# Schematic.net
KiCad netlist of a schematic drawn in EAGLE
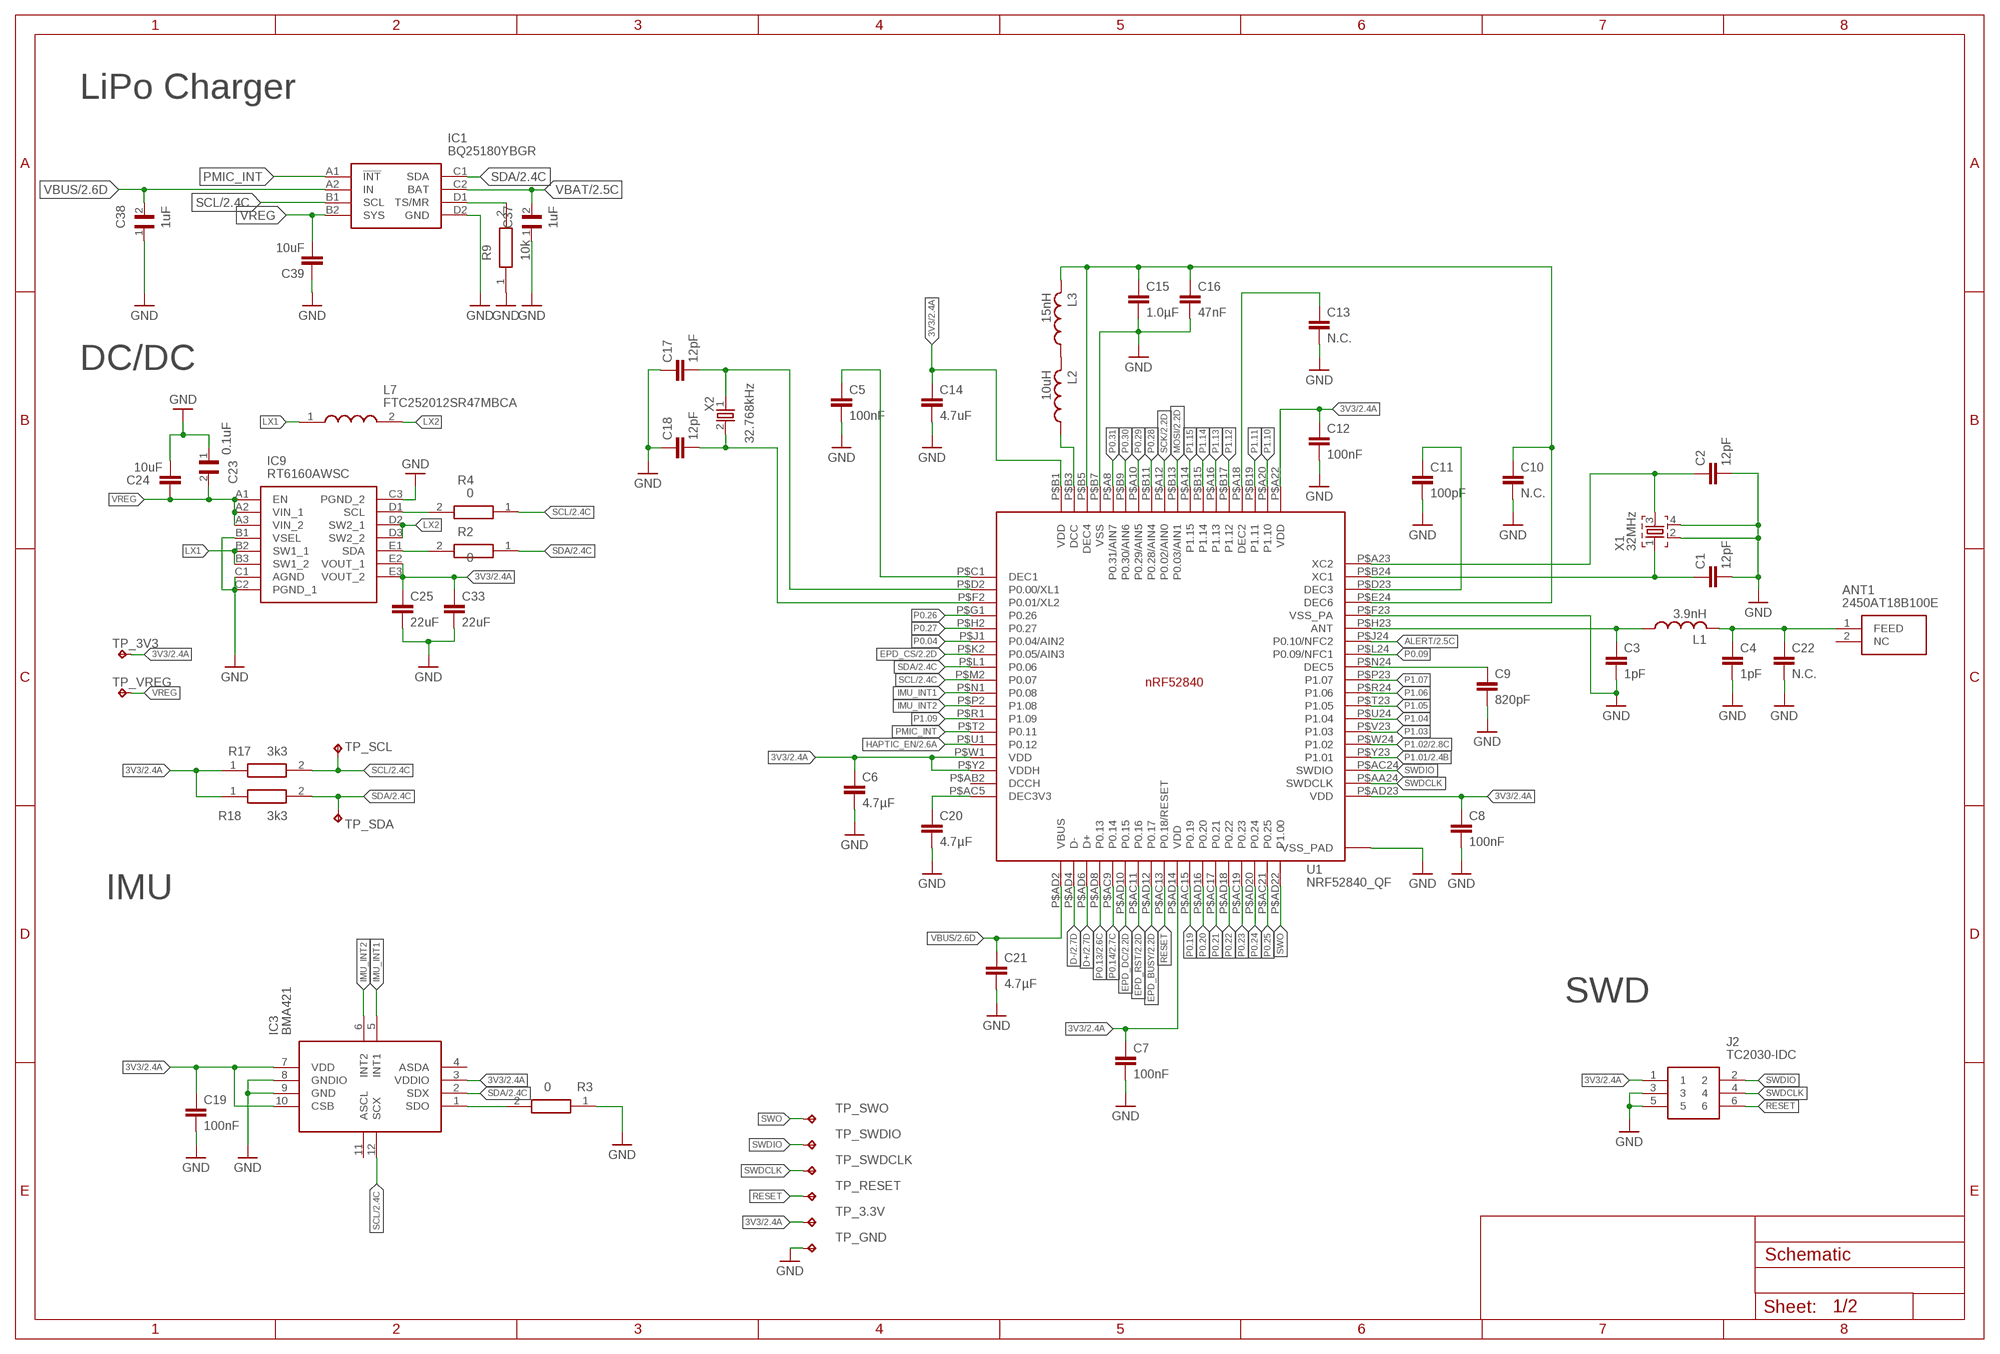
[diagram p0: schematic, sheet 1]
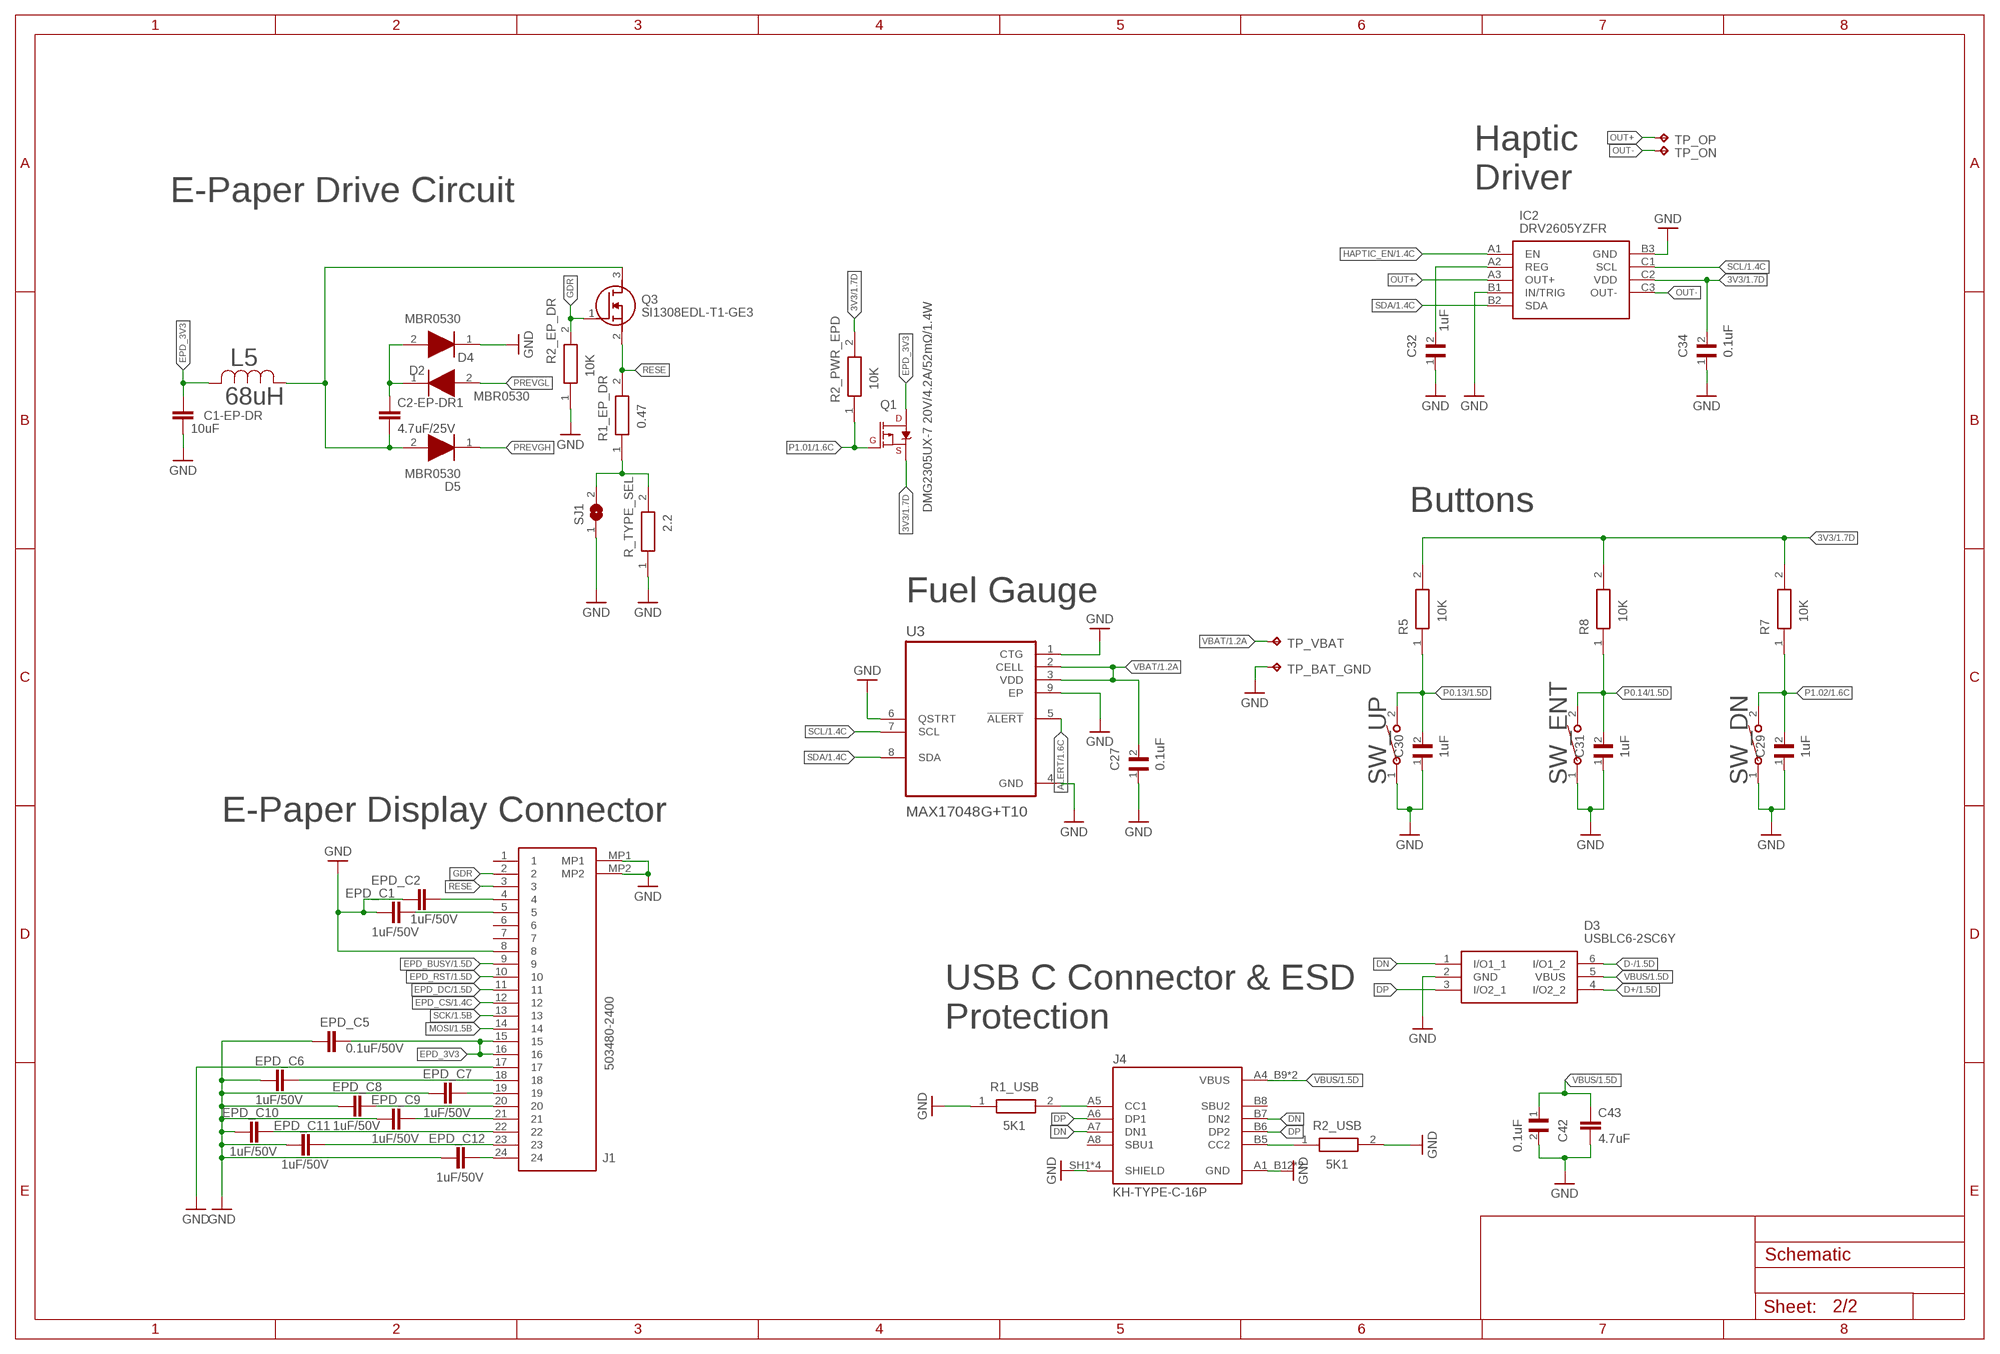
[diagram p1: schematic, sheet 2]

(export (version "E")
  (design (tool "Eeschema 10.0.6"))
  (components
    (comp (ref "ANT1")
      (value "2450AT18B100E")
      (footprint "eagle-import:2450AT18B100E_ANTC3216X140N")
      (fields (field (name "MOUSER_PART_NUMBER") "609-2450AT18B100E"))
      (libsource (lib "eagle-import") (part "2450AT18B100E_2450AT18B100E"))
    )
    (comp (ref "C1")
      (value "12pF")
      (footprint "eagle-import:NORDIC_NRF_3_RESC0201_L")
      (libsource (lib "eagle-import") (part "NORDIC_NRF_3_CAPACITOR_0201_L"))
    )
    (comp (ref "C2")
      (value "12pF")
      (footprint "eagle-import:NORDIC_NRF_3_RESC0201_L")
      (libsource (lib "eagle-import") (part "NORDIC_NRF_3_CAPACITOR_0201_L"))
    )
    (comp (ref "C3")
      (value "1pF")
      (footprint "eagle-import:NORDIC_NRF_3_RESC0201_L")
      (libsource (lib "eagle-import") (part "NORDIC_NRF_3_CAPACITOR_0201_L"))
    )
    (comp (ref "C4")
      (value "1pF")
      (footprint "eagle-import:NORDIC_NRF_3_RESC0201_L")
      (libsource (lib "eagle-import") (part "NORDIC_NRF_3_CAPACITOR_0201_L"))
    )
    (comp (ref "C5")
      (value "100nF")
      (footprint "eagle-import:NORDIC_NRF_3_RESC0201_L")
      (libsource (lib "eagle-import") (part "NORDIC_NRF_3_CAPACITOR_0201_L"))
    )
    (comp (ref "C6")
      (value "4.7µF")
      (footprint "eagle-import:PERFECT_0402_0402")
      (libsource (lib "eagle-import") (part "PERFECT_0402_CAP_0402"))
    )
    (comp (ref "C7")
      (value "100nF")
      (footprint "eagle-import:NORDIC_NRF_3_RESC0201_L")
      (libsource (lib "eagle-import") (part "NORDIC_NRF_3_CAPACITOR_0201_L"))
    )
    (comp (ref "C8")
      (value "100nF")
      (footprint "eagle-import:NORDIC_NRF_3_RESC0201_L")
      (libsource (lib "eagle-import") (part "NORDIC_NRF_3_CAPACITOR_0201_L"))
    )
    (comp (ref "C9")
      (value "820pF")
      (footprint "eagle-import:NORDIC_NRF_3_RESC0201_L")
      (libsource (lib "eagle-import") (part "NORDIC_NRF_3_CAPACITOR_0201_L"))
    )
    (comp (ref "C10")
      (value "N.C.")
      (footprint "eagle-import:NORDIC_NRF_3_RESC0201_L")
      (libsource (lib "eagle-import") (part "NORDIC_NRF_3_CAPACITOR_0201_L"))
    )
    (comp (ref "C11")
      (value "100pF")
      (footprint "eagle-import:NORDIC_NRF_3_RESC0201_L")
      (libsource (lib "eagle-import") (part "NORDIC_NRF_3_CAPACITOR_0201_L"))
    )
    (comp (ref "C12")
      (value "100nF")
      (footprint "eagle-import:NORDIC_NRF_3_RESC0201_L")
      (libsource (lib "eagle-import") (part "NORDIC_NRF_3_CAPACITOR_0201_L"))
    )
    (comp (ref "C13")
      (value "N.C.")
      (footprint "eagle-import:NORDIC_NRF_3_RESC0201_L")
      (libsource (lib "eagle-import") (part "NORDIC_NRF_3_CAPACITOR_0201_L"))
    )
    (comp (ref "C14")
      (value "4.7uF")
      (footprint "eagle-import:PERFECT_0402_0402")
      (libsource (lib "eagle-import") (part "PERFECT_0402_CAP_0402"))
    )
    (comp (ref "C15")
      (value "1.0µF")
      (footprint "eagle-import:PERFECT_0402_0402")
      (libsource (lib "eagle-import") (part "PERFECT_0402_CAP_0402"))
    )
    (comp (ref "C16")
      (value "47nF")
      (footprint "eagle-import:NORDIC_NRF_3_RESC0201_L")
      (libsource (lib "eagle-import") (part "NORDIC_NRF_3_CAPACITOR_0201_L"))
    )
    (comp (ref "C17")
      (value "12pF")
      (footprint "eagle-import:NORDIC_NRF_3_RESC0201_L")
      (libsource (lib "eagle-import") (part "NORDIC_NRF_3_CAPACITOR_0201_L"))
    )
    (comp (ref "C18")
      (value "12pF")
      (footprint "eagle-import:NORDIC_NRF_3_RESC0201_L")
      (libsource (lib "eagle-import") (part "NORDIC_NRF_3_CAPACITOR_0201_L"))
    )
    (comp (ref "C19")
      (value "100nF")
      (footprint "eagle-import:NORDIC_NRF_3_RESC0201_L")
      (libsource (lib "eagle-import") (part "NORDIC_NRF_3_CAPACITOR_0201_L"))
    )
    (comp (ref "C20")
      (value "4.7µF")
      (footprint "eagle-import:PERFECT_0402_0402")
      (libsource (lib "eagle-import") (part "PERFECT_0402_CAP_0402"))
    )
    (comp (ref "C21")
      (value "4.7µF")
      (footprint "eagle-import:PERFECT_0402_0402")
      (libsource (lib "eagle-import") (part "PERFECT_0402_CAP_0402"))
    )
    (comp (ref "C22")
      (value "N.C.")
      (footprint "eagle-import:NORDIC_NRF_3_RESC0201_L")
      (libsource (lib "eagle-import") (part "NORDIC_NRF_3_CAPACITOR_0201_L"))
    )
    (comp (ref "C23")
      (value "0.1uF")
      (footprint "eagle-import:GRM011R60J152KE01L_2_CAPC0201X13N")
      (fields (field (name "MF") "Murata") (field (name "MP") "GRM011R60J152KE01L"))
      (libsource (lib "eagle-import") (part "GRM011R60J152KE01L_2_GRM011R60J152KE01L"))
    )
    (comp (ref "C24")
      (value "10uF")
      (footprint "eagle-import:PERFECT_0402_0402")
      (libsource (lib "eagle-import") (part "PERFECT_0402_CAP_0402"))
    )
    (comp (ref "C25")
      (value "22uF")
      (footprint "eagle-import:PERFECT_0402_0402")
      (libsource (lib "eagle-import") (part "PERFECT_0402_CAP_0402"))
    )
    (comp (ref "C33")
      (value "22uF")
      (footprint "eagle-import:PERFECT_0402_0402")
      (libsource (lib "eagle-import") (part "PERFECT_0402_CAP_0402"))
    )
    (comp (ref "C37")
      (value "1uF")
      (footprint "eagle-import:GRM011R60J152KE01L_2_CAPC0201X13N")
      (fields (field (name "MF") "Murata") (field (name "MP") "GRM011R60J152KE01L"))
      (libsource (lib "eagle-import") (part "GRM011R60J152KE01L_2_GRM011R60J152KE01L"))
    )
    (comp (ref "C38")
      (value "1uF")
      (footprint "eagle-import:GRM011R60J152KE01L_2_CAPC0201X13N")
      (fields (field (name "MF") "Murata") (field (name "MP") "GRM011R60J152KE01L"))
      (libsource (lib "eagle-import") (part "GRM011R60J152KE01L_2_GRM011R60J152KE01L"))
    )
    (comp (ref "C39")
      (value "10uF")
      (footprint "eagle-import:PERFECT_0402_0402")
      (libsource (lib "eagle-import") (part "PERFECT_0402_CAP_0402"))
    )
    (comp (ref "IC1")
      (value "BQ25180YBGR")
      (footprint "eagle-import:BQ25180YBGR_BGA8C40P2X4_100X155X50")
      (fields (field (name "MOUSER_PART_NUMBER") "595-BQ25180YBGR"))
      (libsource (lib "eagle-import") (part "BQ25180YBGR_BQ25180YBGR"))
    )
    (comp (ref "IC3")
      (value "BMA421")
      (footprint "eagle-import:BMA423_BMA423")
      (fields (field (name "ARROW_PART_NUMBER") "BMA423") (field (name "MOUSER_PART_NUMBER") "262-BMA423"))
      (libsource (lib "eagle-import") (part "BMA423_BMA423"))
    )
    (comp (ref "IC9")
      (value "RT6160AWSC")
      (footprint "eagle-import:RT6160AWSC_BGA15C40P3X5_140X230X60")
      (fields (field (name "MOUSER_PART_NUMBER") "835-RT6160AWSC"))
      (libsource (lib "eagle-import") (part "RT6160AWSC_RT6160AWSC"))
    )
    (comp (ref "J2")
      (value "TC2030-IDC")
      (footprint "eagle-import:TC2030-IDC_TC2030IDC")
      (libsource (lib "eagle-import") (part "TC2030-IDC_TC2030-IDC"))
    )
    (comp (ref "L1")
      (value "3.9nH")
      (footprint "eagle-import:NORDIC_NRF_2_RESC0402_L")
      (libsource (lib "eagle-import") (part "NORDIC_NRF_2_INDUCTOR_0402_L"))
    )
    (comp (ref "L2")
      (value "10uH")
      (footprint "eagle-import:NORDIC_NRF_2_RESC0402_L")
      (libsource (lib "eagle-import") (part "NORDIC_NRF_2_INDUCTOR_0402_L"))
    )
    (comp (ref "L3")
      (value "15nH")
      (footprint "eagle-import:NORDIC_NRF_2_RESC0402_L")
      (libsource (lib "eagle-import") (part "NORDIC_NRF_2_INDUCTOR_0402_L"))
    )
    (comp (ref "L7")
      (value "FTC252012SR47MBCA")
      (footprint "eagle-import:MLP2016SR47MT0S1_INDC2016X100N")
      (libsource (lib "eagle-import") (part "MLP2016SR47MT0S1_FTC252012SR47MBCA"))
    )
    (comp (ref "R2")
      (value "0")
      (footprint "eagle-import:CPF0201D7K68C1_0201")
      (libsource (lib "eagle-import") (part "CPF0201D7K68C1_CPF0201D7K68C1"))
    )
    (comp (ref "R3")
      (value "0")
      (footprint "eagle-import:CPF0201D7K68C1_0201")
      (libsource (lib "eagle-import") (part "CPF0201D7K68C1_CPF0201D7K68C1"))
    )
    (comp (ref "R4")
      (value "0")
      (footprint "eagle-import:CPF0201D7K68C1_0201")
      (libsource (lib "eagle-import") (part "CPF0201D7K68C1_CPF0201D7K68C1"))
    )
    (comp (ref "R9")
      (value "10k")
      (footprint "eagle-import:CPF0201D7K68C1_0201")
      (libsource (lib "eagle-import") (part "CPF0201D7K68C1_CPF0201D7K68C1"))
    )
    (comp (ref "R17")
      (value "3k3")
      (footprint "eagle-import:CPF0201D7K68C1_0201")
      (libsource (lib "eagle-import") (part "CPF0201D7K68C1_CPF0201D7K68C1"))
    )
    (comp (ref "R18")
      (value "3k3")
      (footprint "eagle-import:CPF0201D7K68C1_0201")
      (libsource (lib "eagle-import") (part "CPF0201D7K68C1_CPF0201D7K68C1"))
    )
    (comp (ref "TP_3.3V")
      (value "HECTOR_WATCH_1_TPTP20R")
      (footprint "eagle-import:HECTOR_WATCH_1_TP20R")
      (libsource (lib "eagle-import") (part "HECTOR_WATCH_1_TPTP20R"))
    )
    (comp (ref "TP_3V3")
      (value "HECTOR_WATCH_1_TPTP20R")
      (footprint "eagle-import:HECTOR_WATCH_1_TP20R")
      (libsource (lib "eagle-import") (part "HECTOR_WATCH_1_TPTP20R"))
    )
    (comp (ref "TP_GND")
      (value "HECTOR_WATCH_1_TPTP20R")
      (footprint "eagle-import:HECTOR_WATCH_1_TP20R")
      (libsource (lib "eagle-import") (part "HECTOR_WATCH_1_TPTP20R"))
    )
    (comp (ref "TP_RESET")
      (value "HECTOR_WATCH_1_TPTP20R")
      (footprint "eagle-import:HECTOR_WATCH_1_TP20R")
      (libsource (lib "eagle-import") (part "HECTOR_WATCH_1_TPTP20R"))
    )
    (comp (ref "TP_SCL")
      (value "HECTOR_WATCH_1_TPTP20R")
      (footprint "eagle-import:HECTOR_WATCH_1_TP20R")
      (libsource (lib "eagle-import") (part "HECTOR_WATCH_1_TPTP20R"))
    )
    (comp (ref "TP_SDA")
      (value "HECTOR_WATCH_1_TPTP20R")
      (footprint "eagle-import:HECTOR_WATCH_1_TP20R")
      (libsource (lib "eagle-import") (part "HECTOR_WATCH_1_TPTP20R"))
    )
    (comp (ref "TP_SWDCLK")
      (value "HECTOR_WATCH_1_TPTP20R")
      (footprint "eagle-import:HECTOR_WATCH_1_TP20R")
      (libsource (lib "eagle-import") (part "HECTOR_WATCH_1_TPTP20R"))
    )
    (comp (ref "TP_SWDIO")
      (value "HECTOR_WATCH_1_TPTP20R")
      (footprint "eagle-import:HECTOR_WATCH_1_TP20R")
      (libsource (lib "eagle-import") (part "HECTOR_WATCH_1_TPTP20R"))
    )
    (comp (ref "TP_SWO")
      (value "HECTOR_WATCH_1_TPTP20R")
      (footprint "eagle-import:HECTOR_WATCH_1_TP20R")
      (libsource (lib "eagle-import") (part "HECTOR_WATCH_1_TPTP20R"))
    )
    (comp (ref "TP_VREG")
      (value "HECTOR_WATCH_1_TPTP20R")
      (footprint "eagle-import:HECTOR_WATCH_1_TP20R")
      (libsource (lib "eagle-import") (part "HECTOR_WATCH_1_TPTP20R"))
    )
    (comp (ref "U1")
      (value "NRF52840_QF")
      (footprint "eagle-import:NORDIC_NRF_4_AQFN50P700X700X85_HS-74N")
      (libsource (lib "eagle-import") (part "NORDIC_NRF_4_NRF52840_QF"))
    )
    (comp (ref "X1")
      (value "32MHz")
      (footprint "eagle-import:NORDIC_NRF_BT-XTAL_2016_N")
      (libsource (lib "eagle-import") (part "NORDIC_NRF_XTAL_32MHZ"))
    )
    (comp (ref "X2")
      (value "32.768kHz")
      (footprint "eagle-import:NORDIC_NRF_1_XTAL_3215_N")
      (libsource (lib "eagle-import") (part "NORDIC_NRF_1_XTAL_32KHZ"))
    )
    (comp (ref "C1-EP-DR")
      (value "10uF")
      (footprint "eagle-import:PERFECT_0402_0402")
      (libsource (lib "eagle-import") (part "PERFECT_0402_CAP_0402"))
    )
    (comp (ref "C2-EP-DR1")
      (value "4.7uF/25V")
      (footprint "eagle-import:PERFECT_0402_0402")
      (libsource (lib "eagle-import") (part "PERFECT_0402_CAP_0402"))
    )
    (comp (ref "C27")
      (value "0.1uF")
      (footprint "eagle-import:GRM011R60J152KE01L_2_CAPC0201X13N")
      (fields (field (name "MF") "Murata") (field (name "MP") "GRM011R60J152KE01L"))
      (libsource (lib "eagle-import") (part "GRM011R60J152KE01L_2_GRM011R60J152KE01L"))
    )
    (comp (ref "C29")
      (value "1uF")
      (footprint "eagle-import:GRM011R60J152KE01L_2_CAPC0201X13N")
      (fields (field (name "MF") "Murata") (field (name "MP") "GRM011R60J152KE01L"))
      (libsource (lib "eagle-import") (part "GRM011R60J152KE01L_2_GRM011R60J152KE01L"))
    )
    (comp (ref "C30")
      (value "1uF")
      (footprint "eagle-import:GRM011R60J152KE01L_2_CAPC0201X13N")
      (fields (field (name "MF") "Murata") (field (name "MP") "GRM011R60J152KE01L"))
      (libsource (lib "eagle-import") (part "GRM011R60J152KE01L_2_GRM011R60J152KE01L"))
    )
    (comp (ref "C31")
      (value "1uF")
      (footprint "eagle-import:GRM011R60J152KE01L_2_CAPC0201X13N")
      (fields (field (name "MF") "Murata") (field (name "MP") "GRM011R60J152KE01L"))
      (libsource (lib "eagle-import") (part "GRM011R60J152KE01L_2_GRM011R60J152KE01L"))
    )
    (comp (ref "C32")
      (value "1uF")
      (footprint "eagle-import:GRM011R60J152KE01L_2_CAPC0201X13N")
      (fields (field (name "MF") "Murata") (field (name "MP") "GRM011R60J152KE01L"))
      (libsource (lib "eagle-import") (part "GRM011R60J152KE01L_2_GRM011R60J152KE01L"))
    )
    (comp (ref "C34")
      (value "0.1uF")
      (footprint "eagle-import:GRM011R60J152KE01L_2_CAPC0201X13N")
      (fields (field (name "MF") "Murata") (field (name "MP") "GRM011R60J152KE01L"))
      (libsource (lib "eagle-import") (part "GRM011R60J152KE01L_2_GRM011R60J152KE01L"))
    )
    (comp (ref "C42")
      (value "0.1uF")
      (footprint "eagle-import:GRM011R60J152KE01L_2_CAPC0201X13N")
      (fields (field (name "MF") "Murata") (field (name "MP") "GRM011R60J152KE01L"))
      (libsource (lib "eagle-import") (part "GRM011R60J152KE01L_2_GRM011R60J152KE01L"))
    )
    (comp (ref "C43")
      (value "4.7uF")
      (footprint "eagle-import:PERFECT_0402_0402")
      (libsource (lib "eagle-import") (part "PERFECT_0402_CAP_0402"))
    )
    (comp (ref "D2")
      (value "MBR0530")
      (footprint "eagle-import:ESP32_C6_LIBRARY_5_SOD3716X135N")
      (fields (field (name "MF") "ON Semiconductor"))
      (libsource (lib "eagle-import") (part "ESP32_C6_LIBRARY_5_MBR0530"))
    )
    (comp (ref "D3")
      (value "USBLC6-2SC6Y")
      (footprint "eagle-import:ESP32_C6_LIBRARY_3_SOT95P280X145-6N")
      (fields (field (name "MF") "STMicroelectronics"))
      (libsource (lib "eagle-import") (part "ESP32_C6_LIBRARY_3_USBLC6-2SC6Y"))
    )
    (comp (ref "D4")
      (value "MBR0530")
      (footprint "eagle-import:ESP32_C6_LIBRARY_5_SOD3716X135N")
      (fields (field (name "MF") "ON Semiconductor"))
      (libsource (lib "eagle-import") (part "ESP32_C6_LIBRARY_5_MBR0530"))
    )
    (comp (ref "D5")
      (value "MBR0530")
      (footprint "eagle-import:ESP32_C6_LIBRARY_5_SOD3716X135N")
      (fields (field (name "MF") "ON Semiconductor"))
      (libsource (lib "eagle-import") (part "ESP32_C6_LIBRARY_5_MBR0530"))
    )
    (comp (ref "EPD_C1")
      (value "1uF/50V")
      (footprint "eagle-import:PERFECT_0402_0402")
      (libsource (lib "eagle-import") (part "PERFECT_0402_CAP_0402"))
    )
    (comp (ref "EPD_C2")
      (value "1uF/50V")
      (footprint "eagle-import:PERFECT_0402_0402")
      (libsource (lib "eagle-import") (part "PERFECT_0402_CAP_0402"))
    )
    (comp (ref "EPD_C5")
      (value "0.1uF/50V")
      (footprint "eagle-import:NORDIC_NRF_3_RESC0201_L")
      (libsource (lib "eagle-import") (part "NORDIC_NRF_3_CAPACITOR_0201_L"))
    )
    (comp (ref "EPD_C6")
      (value "1uF/50V")
      (footprint "eagle-import:PERFECT_0402_0402")
      (libsource (lib "eagle-import") (part "PERFECT_0402_CAP_0402"))
    )
    (comp (ref "EPD_C7")
      (value "1uF/50V")
      (footprint "eagle-import:PERFECT_0402_0402")
      (libsource (lib "eagle-import") (part "PERFECT_0402_CAP_0402"))
    )
    (comp (ref "EPD_C8")
      (value "1uF/50V")
      (footprint "eagle-import:PERFECT_0402_0402")
      (libsource (lib "eagle-import") (part "PERFECT_0402_CAP_0402"))
    )
    (comp (ref "EPD_C9")
      (value "1uF/50V")
      (footprint "eagle-import:PERFECT_0402_0402")
      (libsource (lib "eagle-import") (part "PERFECT_0402_CAP_0402"))
    )
    (comp (ref "EPD_C10")
      (value "1uF/50V")
      (footprint "eagle-import:PERFECT_0402_0402")
      (libsource (lib "eagle-import") (part "PERFECT_0402_CAP_0402"))
    )
    (comp (ref "EPD_C11")
      (value "1uF/50V")
      (footprint "eagle-import:PERFECT_0402_0402")
      (libsource (lib "eagle-import") (part "PERFECT_0402_CAP_0402"))
    )
    (comp (ref "EPD_C12")
      (value "1uF/50V")
      (footprint "eagle-import:PERFECT_0402_0402")
      (libsource (lib "eagle-import") (part "PERFECT_0402_CAP_0402"))
    )
    (comp (ref "IC2")
      (value "DRV2605YZFR")
      (footprint "eagle-import:DRV2605YZFR_BGA9C50P3X3_144X144X62")
      (libsource (lib "eagle-import") (part "DRV2605YZFR_DRV2605YZFR"))
    )
    (comp (ref "J1")
      (value "503480-2400")
      (footprint "eagle-import:503480-2400_5034802400")
      (fields (field (name "MOUSER_PART_NUMBER") "538-503480-2400"))
      (libsource (lib "eagle-import") (part "503480-2400_503480-2400"))
    )
    (comp (ref "J4")
      (value "KH-TYPE-C-16P")
      (footprint "eagle-import:KH-TYPE-C-16P_KINGHELM_KH-TYPE-C-16P")
      (fields (field (name "MF") "kinghelm"))
      (libsource (lib "eagle-import") (part "KH-TYPE-C-16P_KH-TYPE-C-16P"))
    )
    (comp (ref "L5")
      (value "68uH")
      (footprint "eagle-import:ESP32_C6_LIBRARY_2_IND_4828-WE-TPC_WRE")
      (fields
        (field (name "MANUFACTURER_PART_NUMBER") "744043680")
        (field (name "COPYRIGHT") "Copyright (C) 2024 Ultra Librarian. All rights reserved.")
      )
      (libsource (lib "eagle-import") (part "ESP32_C6_LIBRARY_2_744043680IND_4828-WE-TPC_WRE"))
    )
    (comp (ref "Q1")
      (value "DMG2305UX-7 20V/4.2A/52mΩ/1.4W")
      (footprint "eagle-import:ESP32_C6_LIBRARY_4_ESP32_C6_LIBRARY_4_ESP32_C6_LIBRARY_4_ESP32_C6_LIBRARY_4_ESP32_WROVER_SPARKFUN-DISCRETESEMI_SOT23-3")
      (libsource (lib "eagle-import") (part "ESP32_C6_LIBRARY_4_ESP32_WROVER_SPARKFUN-DISCRETESEMI_MOSFET_PCH-SI2309DS"))
    )
    (comp (ref "Q3")
      (value "SI1308EDL-T1-GE3")
      (footprint "eagle-import:ESP32_C6_LIBRARY_6_SOT65P210X110-3N")
      (fields (field (name "MF") "Vishay Siliconix"))
      (libsource (lib "eagle-import") (part "ESP32_C6_LIBRARY_6_SI1308EDL-T1-GE3"))
    )
    (comp (ref "R1_EP_DR")
      (value "0.47")
      (footprint "eagle-import:CPF0201D7K68C1_0201")
      (libsource (lib "eagle-import") (part "CPF0201D7K68C1_CPF0201D7K68C1"))
    )
    (comp (ref "R1_USB")
      (value "5K1")
      (footprint "eagle-import:CPF0201D7K68C1_0201")
      (libsource (lib "eagle-import") (part "CPF0201D7K68C1_CPF0201D7K68C1"))
    )
    (comp (ref "R2_EP_DR")
      (value "10K")
      (footprint "eagle-import:CPF0201D7K68C1_0201")
      (libsource (lib "eagle-import") (part "CPF0201D7K68C1_CPF0201D7K68C1"))
    )
    (comp (ref "R2_PWR_EPD")
      (value "10K")
      (footprint "eagle-import:CPF0201D7K68C1_0201")
      (libsource (lib "eagle-import") (part "CPF0201D7K68C1_CPF0201D7K68C1"))
    )
    (comp (ref "R2_USB")
      (value "5K1")
      (footprint "eagle-import:CPF0201D7K68C1_0201")
      (libsource (lib "eagle-import") (part "CPF0201D7K68C1_CPF0201D7K68C1"))
    )
    (comp (ref "R5")
      (value "10K")
      (footprint "eagle-import:CPF0201D7K68C1_0201")
      (libsource (lib "eagle-import") (part "CPF0201D7K68C1_CPF0201D7K68C1"))
    )
    (comp (ref "R7")
      (value "10K")
      (footprint "eagle-import:CPF0201D7K68C1_0201")
      (libsource (lib "eagle-import") (part "CPF0201D7K68C1_CPF0201D7K68C1"))
    )
    (comp (ref "R8")
      (value "10K")
      (footprint "eagle-import:CPF0201D7K68C1_0201")
      (libsource (lib "eagle-import") (part "CPF0201D7K68C1_CPF0201D7K68C1"))
    )
    (comp (ref "R_TYPE_SEL")
      (value "2.2")
      (footprint "eagle-import:CPF0201D7K68C1_0201")
      (libsource (lib "eagle-import") (part "CPF0201D7K68C1_CPF0201D7K68C1"))
    )
    (comp (ref "SJ1")
      (value "ESP32_C6_LIBRARY_7_JUMPER_SJ")
      (footprint "eagle-import:ESP32_C6_LIBRARY_7_JUMPER_SJ")
      (libsource (lib "eagle-import") (part "ESP32_C6_LIBRARY_7_JUMPER_SJ"))
    )
    (comp (ref "SW_DN")
      (value "2025-10-22_07-23-44_LIBRARY_EVP-AKE31ASW_EVP-AKE31A_PAN")
      (footprint "eagle-import:2025-10-22_07-23-44_LIBRARY_SW_EVP-AKE31A_PAN")
      (fields
        (field (name "MANUFACTURER_PART_NUMBER") "EVP-AKE31A")
        (field (name "COPYRIGHT") "Copyright (C) 2025 Ultra Librarian. All rights reserved.")
      )
      (libsource (lib "eagle-import") (part "2025-10-22_07-23-44_LIBRARY_EVP-AKE31ASW_EVP-AKE31A_PAN"))
    )
    (comp (ref "SW_ENT")
      (value "2025-10-22_07-23-44_LIBRARY_EVP-AKE31ASW_EVP-AKE31A_PAN")
      (footprint "eagle-import:2025-10-22_07-23-44_LIBRARY_SW_EVP-AKE31A_PAN")
      (fields
        (field (name "MANUFACTURER_PART_NUMBER") "EVP-AKE31A")
        (field (name "COPYRIGHT") "Copyright (C) 2025 Ultra Librarian. All rights reserved.")
      )
      (libsource (lib "eagle-import") (part "2025-10-22_07-23-44_LIBRARY_EVP-AKE31ASW_EVP-AKE31A_PAN"))
    )
    (comp (ref "SW_UP")
      (value "2025-10-22_07-23-44_LIBRARY_EVP-AKE31ASW_EVP-AKE31A_PAN")
      (footprint "eagle-import:2025-10-22_07-23-44_LIBRARY_SW_EVP-AKE31A_PAN")
      (fields
        (field (name "MANUFACTURER_PART_NUMBER") "EVP-AKE31A")
        (field (name "COPYRIGHT") "Copyright (C) 2025 Ultra Librarian. All rights reserved.")
      )
      (libsource (lib "eagle-import") (part "2025-10-22_07-23-44_LIBRARY_EVP-AKE31ASW_EVP-AKE31A_PAN"))
    )
    (comp (ref "TP_BAT_GND")
      (value "HECTOR_WATCH_1_TPTP20R")
      (footprint "eagle-import:HECTOR_WATCH_1_TP20R")
      (libsource (lib "eagle-import") (part "HECTOR_WATCH_1_TPTP20R"))
    )
    (comp (ref "TP_ON")
      (value "HECTOR_WATCH_1_TPTP20R")
      (footprint "eagle-import:HECTOR_WATCH_1_TP20R")
      (libsource (lib "eagle-import") (part "HECTOR_WATCH_1_TPTP20R"))
    )
    (comp (ref "TP_OP")
      (value "HECTOR_WATCH_1_TPTP20R")
      (footprint "eagle-import:HECTOR_WATCH_1_TP20R")
      (libsource (lib "eagle-import") (part "HECTOR_WATCH_1_TPTP20R"))
    )
    (comp (ref "TP_VBAT")
      (value "HECTOR_WATCH_1_TPTP20R")
      (footprint "eagle-import:HECTOR_WATCH_1_TP20R")
      (libsource (lib "eagle-import") (part "HECTOR_WATCH_1_TPTP20R"))
    )
    (comp (ref "U3")
      (value "MAX17048G+T10")
      (footprint "eagle-import:ESP32_C6_LIBRARY_SON50P200X200X80-9N")
      (fields (field (name "MF") "Analog Devices"))
      (libsource (lib "eagle-import") (part "ESP32_C6_LIBRARY_MAX17048G+T10"))
    )
  )
  (nets
    (net (code "1") (name "3V3{slash}1.7D") (class "Default")
      (node (ref "C34") (pin "2") (pinfunction "2_2") (pintype "passive"))
      (node (ref "IC2") (pin "C2") (pinfunction "VDD_C2") (pintype "bidirectional"))
      (node (ref "Q1") (pin "2") (pinfunction "S_2") (pintype "bidirectional"))
      (node (ref "R2_PWR_EPD") (pin "2") (pinfunction "2_2") (pintype "bidirectional"))
      (node (ref "R5") (pin "2") (pinfunction "2_2") (pintype "bidirectional"))
      (node (ref "R7") (pin "2") (pinfunction "2_2") (pintype "bidirectional"))
      (node (ref "R8") (pin "2") (pinfunction "2_2") (pintype "bidirectional"))
    )
    (net (code "2") (name "3V3{slash}2.4A") (class "Default")
      (node (ref "C12") (pin "1") (pinfunction "1_1") (pintype "passive"))
      (node (ref "C14") (pin "1") (pinfunction "1_1") (pintype "passive"))
      (node (ref "C19") (pin "1") (pinfunction "1_1") (pintype "passive"))
      (node (ref "C25") (pin "1") (pinfunction "1_1") (pintype "passive"))
      (node (ref "C33") (pin "1") (pinfunction "1_1") (pintype "passive"))
      (node (ref "C6") (pin "1") (pinfunction "1_1") (pintype "passive"))
      (node (ref "C7") (pin "1") (pinfunction "1_1") (pintype "passive"))
      (node (ref "C8") (pin "1") (pinfunction "1_1") (pintype "passive"))
      (node (ref "IC3") (pin "10") (pinfunction "CSB_10") (pintype "bidirectional"))
      (node (ref "IC3") (pin "3") (pinfunction "VDDIO_3") (pintype "bidirectional"))
      (node (ref "IC3") (pin "7") (pinfunction "VDD_7") (pintype "bidirectional"))
      (node (ref "IC9") (pin "E2") (pinfunction "VOUT_1_E2") (pintype "bidirectional"))
      (node (ref "IC9") (pin "E3") (pinfunction "VOUT_2_E3") (pintype "bidirectional"))
      (node (ref "J2") (pin "1") (pinfunction "1_1") (pintype "bidirectional"))
      (node (ref "R17") (pin "1") (pinfunction "1_1") (pintype "bidirectional"))
      (node (ref "R18") (pin "1") (pinfunction "1_1") (pintype "bidirectional"))
      (node (ref "TP_3.3V") (pin "TP") (pinfunction "TP_TP") (pintype "input"))
      (node (ref "TP_3V3") (pin "TP") (pinfunction "TP_TP") (pintype "input"))
      (node (ref "U1") (pin "P$A22") (pinfunction "VDD_P$A22") (pintype "power_in"))
      (node (ref "U1") (pin "P$AD14") (pinfunction "VDD_P$AD14") (pintype "power_in"))
      (node (ref "U1") (pin "P$AD23") (pinfunction "VDD_P$AD23") (pintype "power_in"))
      (node (ref "U1") (pin "P$B1") (pinfunction "VDD_P$B1") (pintype "power_in"))
      (node (ref "U1") (pin "P$W1") (pinfunction "VDD_P$W1") (pintype "power_in"))
      (node (ref "U1") (pin "P$Y2") (pinfunction "VDDH_P$Y2") (pintype "power_in"))
    )
    (net (code "3") (name "ALERT{slash}1.6C") (class "Default")
      (node (ref "U3") (pin "5") (pinfunction "~{ALERT}_5") (pintype "output"))
    )
    (net (code "4") (name "ALERT{slash}2.5C") (class "Default")
      (node (ref "U1") (pin "P$J24") (pinfunction "P0.10/NFC2_P$J24") (pintype "bidirectional"))
    )
    (net (code "5") (name "D+{slash}1.5D") (class "Default")
      (node (ref "D3") (pin "4") (pinfunction "I/O2_2_4") (pintype "bidirectional"))
    )
    (net (code "6") (name "D+{slash}2.7D") (class "Default")
      (node (ref "U1") (pin "P$AD6") (pinfunction "D+_P$AD6") (pintype "bidirectional"))
    )
    (net (code "7") (name "D-{slash}1.5D") (class "Default")
      (node (ref "D3") (pin "6") (pinfunction "I/O1_2_6") (pintype "bidirectional"))
    )
    (net (code "8") (name "D-{slash}2.7D") (class "Default")
      (node (ref "U1") (pin "P$AD4") (pinfunction "D-_P$AD4") (pintype "bidirectional"))
    )
    (net (code "9") (name "DN") (class "Default")
      (node (ref "D3") (pin "1") (pinfunction "I/O1_1_1") (pintype "bidirectional"))
      (node (ref "J4") (pin "A7") (pinfunction "DN1_A7") (pintype "bidirectional"))
      (node (ref "J4") (pin "B7") (pinfunction "DN2_B7") (pintype "bidirectional"))
    )
    (net (code "10") (name "DP") (class "Default")
      (node (ref "D3") (pin "3") (pinfunction "I/O2_1_3") (pintype "bidirectional"))
      (node (ref "J4") (pin "A6") (pinfunction "DP1_A6") (pintype "bidirectional"))
      (node (ref "J4") (pin "B6") (pinfunction "DP2_B6") (pintype "bidirectional"))
    )
    (net (code "11") (name "EPD_3V3") (class "Default")
      (node (ref "C1-EP-DR") (pin "1") (pinfunction "1_1") (pintype "passive"))
      (node (ref "EPD_C5") (pin "2") (pinfunction "2_2") (pintype "passive"))
      (node (ref "J1") (pin "15") (pinfunction "15_15") (pintype "bidirectional"))
      (node (ref "J1") (pin "16") (pinfunction "16_16") (pintype "bidirectional"))
      (node (ref "L5") (pin "2") (pinfunction "2_2") (pintype "passive"))
      (node (ref "Q1") (pin "3") (pinfunction "D_3") (pintype "bidirectional"))
    )
    (net (code "12") (name "EPD_BUSY{slash}1.5D") (class "Default")
      (node (ref "J1") (pin "9") (pinfunction "9_9") (pintype "bidirectional"))
    )
    (net (code "13") (name "EPD_BUSY{slash}2.2D") (class "Default")
      (node (ref "U1") (pin "P$AD12") (pinfunction "P0.17_P$AD12") (pintype "bidirectional"))
    )
    (net (code "14") (name "EPD_CS{slash}1.4C") (class "Default")
      (node (ref "J1") (pin "12") (pinfunction "12_12") (pintype "bidirectional"))
    )
    (net (code "15") (name "EPD_CS{slash}2.2D") (class "Default")
      (node (ref "U1") (pin "P$K2") (pinfunction "P0.05/AIN3_P$K2") (pintype "bidirectional"))
    )
    (net (code "16") (name "EPD_DC{slash}1.5D") (class "Default")
      (node (ref "J1") (pin "11") (pinfunction "11_11") (pintype "bidirectional"))
    )
    (net (code "17") (name "EPD_DC{slash}2.2D") (class "Default")
      (node (ref "U1") (pin "P$AD10") (pinfunction "P0.15_P$AD10") (pintype "bidirectional"))
    )
    (net (code "18") (name "EPD_RST{slash}1.5D") (class "Default")
      (node (ref "J1") (pin "10") (pinfunction "10_10") (pintype "bidirectional"))
    )
    (net (code "19") (name "EPD_RST{slash}2.2D") (class "Default")
      (node (ref "U1") (pin "P$AC11") (pinfunction "P0.16_P$AC11") (pintype "bidirectional"))
    )
    (net (code "20") (name "GDR") (class "Default")
      (node (ref "J1") (pin "2") (pinfunction "2_2") (pintype "bidirectional"))
      (node (ref "Q3") (pin "1") (pinfunction "G_1") (pintype "bidirectional"))
      (node (ref "R2_EP_DR") (pin "2") (pinfunction "2_2") (pintype "bidirectional"))
    )
    (net (code "21") (name "GND") (class "Default")
      (node (ref "C1") (pin "2") (pinfunction "2_2") (pintype "passive"))
      (node (ref "C1-EP-DR") (pin "2") (pinfunction "2_2") (pintype "passive"))
      (node (ref "C10") (pin "2") (pinfunction "2_2") (pintype "passive"))
      (node (ref "C11") (pin "2") (pinfunction "2_2") (pintype "passive"))
      (node (ref "C12") (pin "2") (pinfunction "2_2") (pintype "passive"))
      (node (ref "C13") (pin "2") (pinfunction "2_2") (pintype "passive"))
      (node (ref "C14") (pin "2") (pinfunction "2_2") (pintype "passive"))
      (node (ref "C15") (pin "2") (pinfunction "2_2") (pintype "passive"))
      (node (ref "C16") (pin "2") (pinfunction "2_2") (pintype "passive"))
      (node (ref "C17") (pin "1") (pinfunction "1_1") (pintype "passive"))
      (node (ref "C18") (pin "1") (pinfunction "1_1") (pintype "passive"))
      (node (ref "C19") (pin "2") (pinfunction "2_2") (pintype "passive"))
      (node (ref "C2") (pin "2") (pinfunction "2_2") (pintype "passive"))
      (node (ref "C20") (pin "2") (pinfunction "2_2") (pintype "passive"))
      (node (ref "C21") (pin "2") (pinfunction "2_2") (pintype "passive"))
      (node (ref "C22") (pin "2") (pinfunction "2_2") (pintype "passive"))
      (node (ref "C23") (pin "1") (pinfunction "1_1") (pintype "passive"))
      (node (ref "C24") (pin "2") (pinfunction "2_2") (pintype "passive"))
      (node (ref "C25") (pin "2") (pinfunction "2_2") (pintype "passive"))
      (node (ref "C27") (pin "1") (pinfunction "1_1") (pintype "passive"))
      (node (ref "C29") (pin "1") (pinfunction "1_1") (pintype "passive"))
      (node (ref "C3") (pin "2") (pinfunction "2_2") (pintype "passive"))
      (node (ref "C30") (pin "1") (pinfunction "1_1") (pintype "passive"))
      (node (ref "C31") (pin "1") (pinfunction "1_1") (pintype "passive"))
      (node (ref "C32") (pin "1") (pinfunction "1_1") (pintype "passive"))
      (node (ref "C33") (pin "2") (pinfunction "2_2") (pintype "passive"))
      (node (ref "C34") (pin "1") (pinfunction "1_1") (pintype "passive"))
      (node (ref "C37") (pin "1") (pinfunction "1_1") (pintype "passive"))
      (node (ref "C38") (pin "1") (pinfunction "1_1") (pintype "passive"))
      (node (ref "C39") (pin "1") (pinfunction "1_1") (pintype "passive"))
      (node (ref "C4") (pin "2") (pinfunction "2_2") (pintype "passive"))
      (node (ref "C42") (pin "2") (pinfunction "2_2") (pintype "passive"))
      (node (ref "C43") (pin "2") (pinfunction "2_2") (pintype "passive"))
      (node (ref "C5") (pin "2") (pinfunction "2_2") (pintype "passive"))
      (node (ref "C6") (pin "2") (pinfunction "2_2") (pintype "passive"))
      (node (ref "C7") (pin "2") (pinfunction "2_2") (pintype "passive"))
      (node (ref "C8") (pin "2") (pinfunction "2_2") (pintype "passive"))
      (node (ref "C9") (pin "2") (pinfunction "2_2") (pintype "passive"))
      (node (ref "D3") (pin "2") (pinfunction "GND_2") (pintype "bidirectional"))
      (node (ref "D4") (pin "1") (pinfunction "K_1") (pintype "bidirectional"))
      (node (ref "EPD_C1") (pin "1") (pinfunction "1_1") (pintype "passive"))
      (node (ref "EPD_C10") (pin "1") (pinfunction "1_1") (pintype "passive"))
      (node (ref "EPD_C11") (pin "1") (pinfunction "1_1") (pintype "passive"))
      (node (ref "EPD_C12") (pin "1") (pinfunction "1_1") (pintype "passive"))
      (node (ref "EPD_C2") (pin "1") (pinfunction "1_1") (pintype "passive"))
      (node (ref "EPD_C5") (pin "1") (pinfunction "1_1") (pintype "passive"))
      (node (ref "EPD_C6") (pin "1") (pinfunction "1_1") (pintype "passive"))
      (node (ref "EPD_C7") (pin "1") (pinfunction "1_1") (pintype "passive"))
      (node (ref "EPD_C8") (pin "1") (pinfunction "1_1") (pintype "passive"))
      (node (ref "EPD_C9") (pin "1") (pinfunction "1_1") (pintype "passive"))
      (node (ref "IC1") (pin "D2") (pinfunction "GND_D2") (pintype "bidirectional"))
      (node (ref "IC2") (pin "B1") (pinfunction "IN/TRIG_B1") (pintype "bidirectional"))
      (node (ref "IC2") (pin "B3") (pinfunction "GND_B3") (pintype "bidirectional"))
      (node (ref "IC3") (pin "8") (pinfunction "GNDIO_8") (pintype "bidirectional"))
      (node (ref "IC3") (pin "9") (pinfunction "GND_9") (pintype "bidirectional"))
      (node (ref "IC9") (pin "B1") (pinfunction "VSEL_B1") (pintype "bidirectional"))
      (node (ref "IC9") (pin "C1") (pinfunction "AGND_C1") (pintype "bidirectional"))
      (node (ref "IC9") (pin "C2") (pinfunction "PGND_1_C2") (pintype "bidirectional"))
      (node (ref "IC9") (pin "C3") (pinfunction "PGND_2_C3") (pintype "bidirectional"))
      (node (ref "J1") (pin "17") (pinfunction "17_17") (pintype "bidirectional"))
      (node (ref "J1") (pin "8") (pinfunction "8_8") (pintype "bidirectional"))
      (node (ref "J1") (pin "MP1") (pinfunction "MP1_MP1") (pintype "bidirectional"))
      (node (ref "J1") (pin "MP2") (pinfunction "MP2_MP2") (pintype "bidirectional"))
      (node (ref "J2") (pin "3") (pinfunction "3_3") (pintype "bidirectional"))
      (node (ref "J2") (pin "5") (pinfunction "5_5") (pintype "bidirectional"))
      (node (ref "J4") (pin "A12_B1") (pinfunction "GND_A12_B1") (pintype "power_in"))
      (node (ref "J4") (pin "A1_B12") (pinfunction "GND_A1_B12") (pintype "power_in"))
      (node (ref "J4") (pin "SH1") (pinfunction "SHIELD_SH1") (pintype "passive"))
      (node (ref "J4") (pin "SH2") (pinfunction "SHIELD_SH2") (pintype "passive"))
      (node (ref "J4") (pin "SH3") (pinfunction "SHIELD_SH3") (pintype "passive"))
      (node (ref "J4") (pin "SH4") (pinfunction "SHIELD_SH4") (pintype "passive"))
      (node (ref "R1_USB") (pin "1") (pinfunction "1_1") (pintype "bidirectional"))
      (node (ref "R2_EP_DR") (pin "1") (pinfunction "1_1") (pintype "bidirectional"))
      (node (ref "R2_USB") (pin "2") (pinfunction "2_2") (pintype "bidirectional"))
      (node (ref "R3") (pin "1") (pinfunction "1_1") (pintype "bidirectional"))
      (node (ref "R9") (pin "1") (pinfunction "1_1") (pintype "bidirectional"))
      (node (ref "R_TYPE_SEL") (pin "1") (pinfunction "1_1") (pintype "bidirectional"))
      (node (ref "SJ1") (pin "1") (pinfunction "1_1") (pintype "passive"))
      (node (ref "SW_DN") (pin "1") (pinfunction "1_1") (pintype "passive"))
      (node (ref "SW_ENT") (pin "1") (pinfunction "1_1") (pintype "passive"))
      (node (ref "SW_UP") (pin "1") (pinfunction "1_1") (pintype "passive"))
      (node (ref "TP_BAT_GND") (pin "TP") (pinfunction "TP_TP") (pintype "input"))
      (node (ref "TP_GND") (pin "TP") (pinfunction "TP_TP") (pintype "input"))
      (node (ref "U1") (pin "P$74") (pinfunction "VSS_PAD_P$74") (pintype "bidirectional"))
      (node (ref "U1") (pin "P$75") (pinfunction "VSS_PAD_P$75") (pintype "bidirectional"))
      (node (ref "U1") (pin "P$76") (pinfunction "VSS_PAD_P$76") (pintype "bidirectional"))
      (node (ref "U1") (pin "P$77") (pinfunction "VSS_PAD_P$77") (pintype "bidirectional"))
      (node (ref "U1") (pin "P$78") (pinfunction "VSS_PAD_P$78") (pintype "bidirectional"))
      (node (ref "U1") (pin "P$79") (pinfunction "VSS_PAD_P$79") (pintype "bidirectional"))
      (node (ref "U1") (pin "P$80") (pinfunction "VSS_PAD_P$80") (pintype "bidirectional"))
      (node (ref "U1") (pin "P$81") (pinfunction "VSS_PAD_P$81") (pintype "bidirectional"))
      (node (ref "U1") (pin "P$82") (pinfunction "VSS_PAD_P$82") (pintype "bidirectional"))
      (node (ref "U1") (pin "P$83") (pinfunction "VSS_PAD_P$83") (pintype "bidirectional"))
      (node (ref "U1") (pin "P$84") (pinfunction "VSS_PAD_P$84") (pintype "bidirectional"))
      (node (ref "U1") (pin "P$85") (pinfunction "VSS_PAD_P$85") (pintype "bidirectional"))
      (node (ref "U1") (pin "P$86") (pinfunction "VSS_PAD_P$86") (pintype "bidirectional"))
      (node (ref "U1") (pin "P$87") (pinfunction "VSS_PAD_P$87") (pintype "bidirectional"))
      (node (ref "U1") (pin "P$88") (pinfunction "VSS_PAD_P$88") (pintype "bidirectional"))
      (node (ref "U1") (pin "P$89") (pinfunction "VSS_PAD_P$89") (pintype "bidirectional"))
      (node (ref "U1") (pin "P$90") (pinfunction "VSS_PAD_P$90") (pintype "bidirectional"))
      (node (ref "U1") (pin "P$B7") (pinfunction "VSS_P$B7") (pintype "power_in"))
      (node (ref "U1") (pin "P$F23") (pinfunction "VSS_PA_P$F23") (pintype "bidirectional"))
      (node (ref "U3") (pin "1") (pinfunction "CTG_1") (pintype "power_in"))
      (node (ref "U3") (pin "4") (pinfunction "GND_4") (pintype "power_in"))
      (node (ref "U3") (pin "6") (pinfunction "QSTRT_6") (pintype "input"))
      (node (ref "U3") (pin "9") (pinfunction "EP_9") (pintype "power_in"))
      (node (ref "X1") (pin "2") (pinfunction "2_2") (pintype "passive"))
      (node (ref "X1") (pin "4") (pinfunction "4_4") (pintype "passive"))
    )
    (net (code "22") (name "HAPTIC_EN{slash}1.4C") (class "Default")
      (node (ref "IC2") (pin "A1") (pinfunction "EN_A1") (pintype "bidirectional"))
    )
    (net (code "23") (name "HAPTIC_EN{slash}2.6A") (class "Default")
      (node (ref "U1") (pin "P$U1") (pinfunction "P0.12_P$U1") (pintype "bidirectional"))
    )
    (net (code "24") (name "IMU_INT1") (class "Default")
      (node (ref "IC3") (pin "5") (pinfunction "INT1_5") (pintype "bidirectional"))
      (node (ref "U1") (pin "P$N1") (pinfunction "P0.08_P$N1") (pintype "bidirectional"))
    )
    (net (code "25") (name "IMU_INT2") (class "Default")
      (node (ref "IC3") (pin "6") (pinfunction "INT2_6") (pintype "bidirectional"))
      (node (ref "U1") (pin "P$P2") (pinfunction "P1.08_P$P2") (pintype "bidirectional"))
    )
    (net (code "26") (name "LX1") (class "Default")
      (node (ref "IC9") (pin "B2") (pinfunction "SW1_1_B2") (pintype "bidirectional"))
      (node (ref "IC9") (pin "B3") (pinfunction "SW1_2_B3") (pintype "bidirectional"))
      (node (ref "L7") (pin "1") (pinfunction "1_1") (pintype "bidirectional"))
    )
    (net (code "27") (name "LX2") (class "Default")
      (node (ref "IC9") (pin "D2") (pinfunction "SW2_1_D2") (pintype "bidirectional"))
      (node (ref "IC9") (pin "D3") (pinfunction "SW2_2_D3") (pintype "bidirectional"))
      (node (ref "L7") (pin "2") (pinfunction "2_2") (pintype "bidirectional"))
    )
    (net (code "28") (name "MOSI{slash}1.5B") (class "Default")
      (node (ref "J1") (pin "14") (pinfunction "14_14") (pintype "bidirectional"))
    )
    (net (code "29") (name "MOSI{slash}2.2D") (class "Default")
      (node (ref "U1") (pin "P$B13") (pinfunction "P0.03/AIN1_P$B13") (pintype "bidirectional"))
    )
    (net (code "30") (name "Net-(ANT1-FEED)") (class "Default")
      (node (ref "ANT1") (pin "1") (pinfunction "FEED_1") (pintype "input"))
      (node (ref "C22") (pin "1") (pinfunction "1_1") (pintype "passive"))
      (node (ref "C4") (pin "1") (pinfunction "1_1") (pintype "passive"))
      (node (ref "L1") (pin "2") (pinfunction "2_2") (pintype "passive"))
    )
    (net (code "31") (name "Net-(D2-K)") (class "Default")
      (node (ref "C2-EP-DR1") (pin "1") (pinfunction "1_1") (pintype "passive"))
      (node (ref "D2") (pin "1") (pinfunction "K_1") (pintype "bidirectional"))
      (node (ref "D4") (pin "2") (pinfunction "A_2") (pintype "bidirectional"))
    )
    (net (code "32") (name "Net-(D5-A)") (class "Default")
      (node (ref "C2-EP-DR1") (pin "2") (pinfunction "2_2") (pintype "passive"))
      (node (ref "D5") (pin "2") (pinfunction "A_2") (pintype "bidirectional"))
      (node (ref "L5") (pin "1") (pinfunction "1_1") (pintype "passive"))
      (node (ref "Q3") (pin "3") (pinfunction "D_3") (pintype "bidirectional"))
    )
    (net (code "33") (name "Net-(EPD_C1-Pad2)") (class "Default")
      (node (ref "EPD_C1") (pin "2") (pinfunction "2_2") (pintype "passive"))
      (node (ref "J1") (pin "5") (pinfunction "5_5") (pintype "bidirectional"))
    )
    (net (code "34") (name "Net-(EPD_C2-Pad2)") (class "Default")
      (node (ref "EPD_C2") (pin "2") (pinfunction "2_2") (pintype "passive"))
      (node (ref "J1") (pin "4") (pinfunction "4_4") (pintype "bidirectional"))
    )
    (net (code "35") (name "Net-(EPD_C6-Pad2)") (class "Default")
      (node (ref "EPD_C6") (pin "2") (pinfunction "2_2") (pintype "passive"))
      (node (ref "J1") (pin "18") (pinfunction "18_18") (pintype "bidirectional"))
    )
    (net (code "36") (name "Net-(EPD_C7-Pad2)") (class "Default")
      (node (ref "EPD_C7") (pin "2") (pinfunction "2_2") (pintype "passive"))
      (node (ref "J1") (pin "19") (pinfunction "19_19") (pintype "bidirectional"))
    )
    (net (code "37") (name "Net-(EPD_C8-Pad2)") (class "Default")
      (node (ref "EPD_C8") (pin "2") (pinfunction "2_2") (pintype "passive"))
      (node (ref "J1") (pin "20") (pinfunction "20_20") (pintype "bidirectional"))
    )
    (net (code "38") (name "Net-(EPD_C9-Pad2)") (class "Default")
      (node (ref "EPD_C9") (pin "2") (pinfunction "2_2") (pintype "passive"))
      (node (ref "J1") (pin "21") (pinfunction "21_21") (pintype "bidirectional"))
    )
    (net (code "39") (name "Net-(EPD_C10-Pad2)") (class "Default")
      (node (ref "EPD_C10") (pin "2") (pinfunction "2_2") (pintype "passive"))
      (node (ref "J1") (pin "22") (pinfunction "22_22") (pintype "bidirectional"))
    )
    (net (code "40") (name "Net-(EPD_C11-Pad2)") (class "Default")
      (node (ref "EPD_C11") (pin "2") (pinfunction "2_2") (pintype "passive"))
      (node (ref "J1") (pin "23") (pinfunction "23_23") (pintype "bidirectional"))
    )
    (net (code "41") (name "Net-(EPD_C12-Pad2)") (class "Default")
      (node (ref "EPD_C12") (pin "2") (pinfunction "2_2") (pintype "passive"))
      (node (ref "J1") (pin "24") (pinfunction "24_24") (pintype "bidirectional"))
    )
    (net (code "42") (name "Net-(IC1-TS{slash}MR)") (class "Default")
      (node (ref "IC1") (pin "D1") (pinfunction "TS/MR_D1") (pintype "bidirectional"))
      (node (ref "R9") (pin "2") (pinfunction "2_2") (pintype "bidirectional"))
    )
    (net (code "43") (name "Net-(IC2-REG)") (class "Default")
      (node (ref "C32") (pin "2") (pinfunction "2_2") (pintype "passive"))
      (node (ref "IC2") (pin "A2") (pinfunction "REG_A2") (pintype "bidirectional"))
    )
    (net (code "44") (name "Net-(IC3-SDO)") (class "Default")
      (node (ref "IC3") (pin "1") (pinfunction "SDO_1") (pintype "bidirectional"))
      (node (ref "R3") (pin "2") (pinfunction "2_2") (pintype "bidirectional"))
    )
    (net (code "45") (name "Net-(IC9-SCL)") (class "Default")
      (node (ref "IC9") (pin "D1") (pinfunction "SCL_D1") (pintype "bidirectional"))
      (node (ref "R4") (pin "2") (pinfunction "2_2") (pintype "bidirectional"))
    )
    (net (code "46") (name "Net-(IC9-SDA)") (class "Default")
      (node (ref "IC9") (pin "E1") (pinfunction "SDA_E1") (pintype "bidirectional"))
      (node (ref "R2") (pin "2") (pinfunction "2_2") (pintype "bidirectional"))
    )
    (net (code "47") (name "Net-(J4-CC1)") (class "Default")
      (node (ref "J4") (pin "A5") (pinfunction "CC1_A5") (pintype "bidirectional"))
      (node (ref "R1_USB") (pin "2") (pinfunction "2_2") (pintype "bidirectional"))
    )
    (net (code "48") (name "Net-(J4-CC2)") (class "Default")
      (node (ref "J4") (pin "B5") (pinfunction "CC2_B5") (pintype "bidirectional"))
      (node (ref "R2_USB") (pin "1") (pinfunction "1_1") (pintype "bidirectional"))
    )
    (net (code "49") (name "Net-(L2-Pad2)") (class "Default")
      (node (ref "L2") (pin "2") (pinfunction "2_2") (pintype "passive"))
      (node (ref "L3") (pin "1") (pinfunction "1_1") (pintype "passive"))
    )
    (net (code "50") (name "Net-(R1_EP_DR-Pad1)") (class "Default")
      (node (ref "R1_EP_DR") (pin "1") (pinfunction "1_1") (pintype "bidirectional"))
      (node (ref "R_TYPE_SEL") (pin "2") (pinfunction "2_2") (pintype "bidirectional"))
      (node (ref "SJ1") (pin "2") (pinfunction "2_2") (pintype "passive"))
    )
    (net (code "51") (name "Net-(U1-ANT)") (class "Default")
      (node (ref "C3") (pin "1") (pinfunction "1_1") (pintype "passive"))
      (node (ref "L1") (pin "1") (pinfunction "1_1") (pintype "passive"))
      (node (ref "U1") (pin "P$H23") (pinfunction "ANT_P$H23") (pintype "bidirectional"))
    )
    (net (code "52") (name "Net-(U1-DCC)") (class "Default")
      (node (ref "L2") (pin "1") (pinfunction "1_1") (pintype "passive"))
      (node (ref "U1") (pin "P$B3") (pinfunction "DCC_P$B3") (pintype "output"))
    )
    (net (code "53") (name "Net-(U1-DEC1)") (class "Default")
      (node (ref "C5") (pin "1") (pinfunction "1_1") (pintype "passive"))
      (node (ref "U1") (pin "P$C1") (pinfunction "DEC1_P$C1") (pintype "power_in"))
    )
    (net (code "54") (name "Net-(U1-DEC2)") (class "Default")
      (node (ref "C13") (pin "1") (pinfunction "1_1") (pintype "passive"))
      (node (ref "U1") (pin "P$A18") (pinfunction "DEC2_P$A18") (pintype "bidirectional"))
    )
    (net (code "55") (name "Net-(U1-DEC3)") (class "Default")
      (node (ref "C11") (pin "1") (pinfunction "1_1") (pintype "passive"))
      (node (ref "U1") (pin "P$D23") (pinfunction "DEC3_P$D23") (pintype "bidirectional"))
    )
    (net (code "56") (name "Net-(U1-DEC3V3)") (class "Default")
      (node (ref "C20") (pin "1") (pinfunction "1_1") (pintype "passive"))
      (node (ref "U1") (pin "P$AC5") (pinfunction "DEC3V3_P$AC5") (pintype "bidirectional"))
    )
    (net (code "57") (name "Net-(U1-DEC4)") (class "Default")
      (node (ref "C10") (pin "1") (pinfunction "1_1") (pintype "passive"))
      (node (ref "C15") (pin "1") (pinfunction "1_1") (pintype "passive"))
      (node (ref "C16") (pin "1") (pinfunction "1_1") (pintype "passive"))
      (node (ref "L3") (pin "2") (pinfunction "2_2") (pintype "passive"))
      (node (ref "U1") (pin "P$B5") (pinfunction "DEC4_P$B5") (pintype "power_in"))
      (node (ref "U1") (pin "P$E24") (pinfunction "DEC6_P$E24") (pintype "bidirectional"))
    )
    (net (code "58") (name "Net-(U1-DEC5)") (class "Default")
      (node (ref "C9") (pin "1") (pinfunction "1_1") (pintype "passive"))
      (node (ref "U1") (pin "P$N24") (pinfunction "DEC5_P$N24") (pintype "bidirectional"))
    )
    (net (code "59") (name "Net-(U1-P0.00{slash}XL1)") (class "Default")
      (node (ref "C17") (pin "2") (pinfunction "2_2") (pintype "passive"))
      (node (ref "U1") (pin "P$D2") (pinfunction "P0.00/XL1_P$D2") (pintype "bidirectional"))
      (node (ref "X2") (pin "1") (pinfunction "1_1") (pintype "passive"))
    )
    (net (code "60") (name "Net-(U1-P0.01{slash}XL2)") (class "Default")
      (node (ref "C18") (pin "2") (pinfunction "2_2") (pintype "passive"))
      (node (ref "U1") (pin "P$F2") (pinfunction "P0.01/XL2_P$F2") (pintype "bidirectional"))
      (node (ref "X2") (pin "2") (pinfunction "2_2") (pintype "passive"))
    )
    (net (code "61") (name "Net-(U1-XC1)") (class "Default")
      (node (ref "C1") (pin "1") (pinfunction "1_1") (pintype "passive"))
      (node (ref "U1") (pin "P$B24") (pinfunction "XC1_P$B24") (pintype "input"))
      (node (ref "X1") (pin "1") (pinfunction "1_1") (pintype "passive"))
    )
    (net (code "62") (name "Net-(U1-XC2)") (class "Default")
      (node (ref "C2") (pin "1") (pinfunction "1_1") (pintype "passive"))
      (node (ref "U1") (pin "P$A23") (pinfunction "XC2_P$A23") (pintype "output"))
      (node (ref "X1") (pin "3") (pinfunction "3_3") (pintype "passive"))
    )
    (net (code "63") (name "OUT+") (class "Default")
      (node (ref "IC2") (pin "A3") (pinfunction "OUT+_A3") (pintype "bidirectional"))
      (node (ref "TP_OP") (pin "TP") (pinfunction "TP_TP") (pintype "input"))
    )
    (net (code "64") (name "OUT-") (class "Default")
      (node (ref "IC2") (pin "C3") (pinfunction "OUT-_C3") (pintype "bidirectional"))
      (node (ref "TP_ON") (pin "TP") (pinfunction "TP_TP") (pintype "input"))
    )
    (net (code "65") (name "P0.04") (class "Default")
      (node (ref "U1") (pin "P$J1") (pinfunction "P0.04/AIN2_P$J1") (pintype "bidirectional"))
    )
    (net (code "66") (name "P0.09") (class "Default")
      (node (ref "U1") (pin "P$L24") (pinfunction "P0.09/NFC1_P$L24") (pintype "bidirectional"))
    )
    (net (code "67") (name "P0.13{slash}1.5D") (class "Default")
      (node (ref "C30") (pin "2") (pinfunction "2_2") (pintype "passive"))
      (node (ref "R5") (pin "1") (pinfunction "1_1") (pintype "bidirectional"))
      (node (ref "SW_UP") (pin "2") (pinfunction "2_2") (pintype "passive"))
    )
    (net (code "68") (name "P0.13{slash}2.6C") (class "Default")
      (node (ref "U1") (pin "P$AD8") (pinfunction "P0.13_P$AD8") (pintype "bidirectional"))
    )
    (net (code "69") (name "P0.14{slash}1.5D") (class "Default")
      (node (ref "C31") (pin "2") (pinfunction "2_2") (pintype "passive"))
      (node (ref "R8") (pin "1") (pinfunction "1_1") (pintype "bidirectional"))
      (node (ref "SW_ENT") (pin "2") (pinfunction "2_2") (pintype "passive"))
    )
    (net (code "70") (name "P0.14{slash}2.7C") (class "Default")
      (node (ref "U1") (pin "P$AC9") (pinfunction "P0.14_P$AC9") (pintype "bidirectional"))
    )
    (net (code "71") (name "P0.19") (class "Default")
      (node (ref "U1") (pin "P$AC15") (pinfunction "P0.19_P$AC15") (pintype "bidirectional"))
    )
    (net (code "72") (name "P0.20") (class "Default")
      (node (ref "U1") (pin "P$AD16") (pinfunction "P0.20_P$AD16") (pintype "bidirectional"))
    )
    (net (code "73") (name "P0.21") (class "Default")
      (node (ref "U1") (pin "P$AC17") (pinfunction "P0.21_P$AC17") (pintype "bidirectional"))
    )
    (net (code "74") (name "P0.22") (class "Default")
      (node (ref "U1") (pin "P$AD18") (pinfunction "P0.22_P$AD18") (pintype "bidirectional"))
    )
    (net (code "75") (name "P0.23") (class "Default")
      (node (ref "U1") (pin "P$AC19") (pinfunction "P0.23_P$AC19") (pintype "bidirectional"))
    )
    (net (code "76") (name "P0.24") (class "Default")
      (node (ref "U1") (pin "P$AD20") (pinfunction "P0.24_P$AD20") (pintype "bidirectional"))
    )
    (net (code "77") (name "P0.25") (class "Default")
      (node (ref "U1") (pin "P$AC21") (pinfunction "P0.25_P$AC21") (pintype "bidirectional"))
    )
    (net (code "78") (name "P0.26") (class "Default")
      (node (ref "U1") (pin "P$G1") (pinfunction "P0.26_P$G1") (pintype "bidirectional"))
    )
    (net (code "79") (name "P0.27") (class "Default")
      (node (ref "U1") (pin "P$H2") (pinfunction "P0.27_P$H2") (pintype "bidirectional"))
    )
    (net (code "80") (name "P0.28") (class "Default")
      (node (ref "U1") (pin "P$B11") (pinfunction "P0.28/AIN4_P$B11") (pintype "bidirectional"))
    )
    (net (code "81") (name "P0.29") (class "Default")
      (node (ref "U1") (pin "P$A10") (pinfunction "P0.29/AIN5_P$A10") (pintype "bidirectional"))
    )
    (net (code "82") (name "P0.30") (class "Default")
      (node (ref "U1") (pin "P$B9") (pinfunction "P0.30/AIN6_P$B9") (pintype "bidirectional"))
    )
    (net (code "83") (name "P0.31") (class "Default")
      (node (ref "U1") (pin "P$A8") (pinfunction "P0.31/AIN7_P$A8") (pintype "bidirectional"))
    )
    (net (code "84") (name "P1.01{slash}1.6C") (class "Default")
      (node (ref "Q1") (pin "1") (pinfunction "G_1") (pintype "bidirectional"))
      (node (ref "R2_PWR_EPD") (pin "1") (pinfunction "1_1") (pintype "bidirectional"))
    )
    (net (code "85") (name "P1.01{slash}2.4B") (class "Default")
      (node (ref "U1") (pin "P$Y23") (pinfunction "P1.01_P$Y23") (pintype "bidirectional"))
    )
    (net (code "86") (name "P1.02{slash}1.6C") (class "Default")
      (node (ref "C29") (pin "2") (pinfunction "2_2") (pintype "passive"))
      (node (ref "R7") (pin "1") (pinfunction "1_1") (pintype "bidirectional"))
      (node (ref "SW_DN") (pin "2") (pinfunction "2_2") (pintype "passive"))
    )
    (net (code "87") (name "P1.02{slash}2.8C") (class "Default")
      (node (ref "U1") (pin "P$W24") (pinfunction "P1.02_P$W24") (pintype "bidirectional"))
    )
    (net (code "88") (name "P1.03") (class "Default")
      (node (ref "U1") (pin "P$V23") (pinfunction "P1.03_P$V23") (pintype "bidirectional"))
    )
    (net (code "89") (name "P1.04") (class "Default")
      (node (ref "U1") (pin "P$U24") (pinfunction "P1.04_P$U24") (pintype "bidirectional"))
    )
    (net (code "90") (name "P1.05") (class "Default")
      (node (ref "U1") (pin "P$T23") (pinfunction "P1.05_P$T23") (pintype "bidirectional"))
    )
    (net (code "91") (name "P1.06") (class "Default")
      (node (ref "U1") (pin "P$R24") (pinfunction "P1.06_P$R24") (pintype "bidirectional"))
    )
    (net (code "92") (name "P1.07") (class "Default")
      (node (ref "U1") (pin "P$P23") (pinfunction "P1.07_P$P23") (pintype "bidirectional"))
    )
    (net (code "93") (name "P1.09") (class "Default")
      (node (ref "U1") (pin "P$R1") (pinfunction "P1.09_P$R1") (pintype "bidirectional"))
    )
    (net (code "94") (name "P1.10") (class "Default")
      (node (ref "U1") (pin "P$A20") (pinfunction "P1.10_P$A20") (pintype "bidirectional"))
    )
    (net (code "95") (name "P1.11") (class "Default")
      (node (ref "U1") (pin "P$B19") (pinfunction "P1.11_P$B19") (pintype "bidirectional"))
    )
    (net (code "96") (name "P1.12") (class "Default")
      (node (ref "U1") (pin "P$B17") (pinfunction "P1.12_P$B17") (pintype "bidirectional"))
    )
    (net (code "97") (name "P1.13") (class "Default")
      (node (ref "U1") (pin "P$A16") (pinfunction "P1.13_P$A16") (pintype "bidirectional"))
    )
    (net (code "98") (name "P1.14") (class "Default")
      (node (ref "U1") (pin "P$B15") (pinfunction "P1.14_P$B15") (pintype "bidirectional"))
    )
    (net (code "99") (name "P1.15") (class "Default")
      (node (ref "U1") (pin "P$A14") (pinfunction "P1.15_P$A14") (pintype "bidirectional"))
    )
    (net (code "100") (name "PMIC_INT") (class "Default")
      (node (ref "IC1") (pin "A1") (pinfunction "~{INT}_A1") (pintype "bidirectional"))
      (node (ref "U1") (pin "P$T2") (pinfunction "P0.11_P$T2") (pintype "bidirectional"))
    )
    (net (code "101") (name "PREVGH") (class "Default")
      (node (ref "D5") (pin "1") (pinfunction "K_1") (pintype "bidirectional"))
    )
    (net (code "102") (name "PREVGL") (class "Default")
      (node (ref "D2") (pin "2") (pinfunction "A_2") (pintype "bidirectional"))
    )
    (net (code "103") (name "RESE") (class "Default")
      (node (ref "J1") (pin "3") (pinfunction "3_3") (pintype "bidirectional"))
      (node (ref "Q3") (pin "2") (pinfunction "S_2") (pintype "bidirectional"))
      (node (ref "R1_EP_DR") (pin "2") (pinfunction "2_2") (pintype "bidirectional"))
    )
    (net (code "104") (name "RESET") (class "Default")
      (node (ref "J2") (pin "6") (pinfunction "6_6") (pintype "bidirectional"))
      (node (ref "TP_RESET") (pin "TP") (pinfunction "TP_TP") (pintype "input"))
      (node (ref "U1") (pin "P$AC13") (pinfunction "P0.18/RESET_P$AC13") (pintype "bidirectional"))
    )
    (net (code "105") (name "SCK{slash}1.5B") (class "Default")
      (node (ref "J1") (pin "13") (pinfunction "13_13") (pintype "bidirectional"))
    )
    (net (code "106") (name "SCK{slash}2.2D") (class "Default")
      (node (ref "U1") (pin "P$A12") (pinfunction "P0.02/AIN0_P$A12") (pintype "bidirectional"))
    )
    (net (code "107") (name "SCL{slash}1.4C") (class "Default")
      (node (ref "IC2") (pin "C1") (pinfunction "SCL_C1") (pintype "bidirectional"))
      (node (ref "U3") (pin "7") (pinfunction "SCL_7") (pintype "input"))
    )
    (net (code "108") (name "SCL{slash}2.4C") (class "Default")
      (node (ref "IC1") (pin "B1") (pinfunction "SCL_B1") (pintype "bidirectional"))
      (node (ref "IC3") (pin "12") (pinfunction "SCX_12") (pintype "bidirectional"))
      (node (ref "R17") (pin "2") (pinfunction "2_2") (pintype "bidirectional"))
      (node (ref "R4") (pin "1") (pinfunction "1_1") (pintype "bidirectional"))
      (node (ref "TP_SCL") (pin "TP") (pinfunction "TP_TP") (pintype "input"))
      (node (ref "U1") (pin "P$M2") (pinfunction "P0.07_P$M2") (pintype "bidirectional"))
    )
    (net (code "109") (name "SDA{slash}1.4C") (class "Default")
      (node (ref "IC2") (pin "B2") (pinfunction "SDA_B2") (pintype "bidirectional"))
      (node (ref "U3") (pin "8") (pinfunction "SDA_8") (pintype "bidirectional"))
    )
    (net (code "110") (name "SDA{slash}2.4C") (class "Default")
      (node (ref "IC1") (pin "C1") (pinfunction "SDA_C1") (pintype "bidirectional"))
      (node (ref "IC3") (pin "2") (pinfunction "SDX_2") (pintype "bidirectional"))
      (node (ref "R18") (pin "2") (pinfunction "2_2") (pintype "bidirectional"))
      (node (ref "R2") (pin "1") (pinfunction "1_1") (pintype "bidirectional"))
      (node (ref "TP_SDA") (pin "TP") (pinfunction "TP_TP") (pintype "input"))
      (node (ref "U1") (pin "P$L1") (pinfunction "P0.06_P$L1") (pintype "bidirectional"))
    )
    (net (code "111") (name "SWDCLK") (class "Default")
      (node (ref "J2") (pin "4") (pinfunction "4_4") (pintype "bidirectional"))
      (node (ref "TP_SWDCLK") (pin "TP") (pinfunction "TP_TP") (pintype "input"))
      (node (ref "U1") (pin "P$AA24") (pinfunction "SWDCLK_P$AA24") (pintype "input"))
    )
    (net (code "112") (name "SWDIO") (class "Default")
      (node (ref "J2") (pin "2") (pinfunction "2_2") (pintype "bidirectional"))
      (node (ref "TP_SWDIO") (pin "TP") (pinfunction "TP_TP") (pintype "input"))
      (node (ref "U1") (pin "P$AC24") (pinfunction "SWDIO_P$AC24") (pintype "bidirectional"))
    )
    (net (code "113") (name "SWO") (class "Default")
      (node (ref "TP_SWO") (pin "TP") (pinfunction "TP_TP") (pintype "input"))
      (node (ref "U1") (pin "P$AD22") (pinfunction "P1.00_P$AD22") (pintype "bidirectional"))
    )
    (net (code "114") (name "VBAT{slash}1.2A") (class "Default")
      (node (ref "C27") (pin "2") (pinfunction "2_2") (pintype "passive"))
      (node (ref "TP_VBAT") (pin "TP") (pinfunction "TP_TP") (pintype "input"))
      (node (ref "U3") (pin "2") (pinfunction "CELL_2") (pintype "power_in"))
      (node (ref "U3") (pin "3") (pinfunction "VDD_3") (pintype "power_in"))
    )
    (net (code "115") (name "VBAT{slash}2.5C") (class "Default")
      (node (ref "C37") (pin "2") (pinfunction "2_2") (pintype "passive"))
      (node (ref "IC1") (pin "C2") (pinfunction "BAT_C2") (pintype "bidirectional"))
    )
    (net (code "116") (name "VBUS{slash}1.5D") (class "Default")
      (node (ref "C42") (pin "1") (pinfunction "1_1") (pintype "passive"))
      (node (ref "C43") (pin "1") (pinfunction "1_1") (pintype "passive"))
      (node (ref "D3") (pin "5") (pinfunction "VBUS_5") (pintype "bidirectional"))
      (node (ref "J4") (pin "A4_B9") (pinfunction "VBUS_A4_B9") (pintype "power_in"))
      (node (ref "J4") (pin "A9_B4") (pinfunction "VBUS_A9_B4") (pintype "power_in"))
    )
    (net (code "117") (name "VBUS{slash}2.6D") (class "Default")
      (node (ref "C21") (pin "1") (pinfunction "1_1") (pintype "passive"))
      (node (ref "C38") (pin "2") (pinfunction "2_2") (pintype "passive"))
      (node (ref "IC1") (pin "A2") (pinfunction "IN_A2") (pintype "bidirectional"))
      (node (ref "U1") (pin "P$AD2") (pinfunction "VBUS_P$AD2") (pintype "power_in"))
    )
    (net (code "118") (name "VREG") (class "Default")
      (node (ref "C23") (pin "2") (pinfunction "2_2") (pintype "passive"))
      (node (ref "C24") (pin "1") (pinfunction "1_1") (pintype "passive"))
      (node (ref "C39") (pin "2") (pinfunction "2_2") (pintype "passive"))
      (node (ref "IC1") (pin "B2") (pinfunction "SYS_B2") (pintype "bidirectional"))
      (node (ref "IC9") (pin "A1") (pinfunction "EN_A1") (pintype "bidirectional"))
      (node (ref "IC9") (pin "A2") (pinfunction "VIN_1_A2") (pintype "bidirectional"))
      (node (ref "IC9") (pin "A3") (pinfunction "VIN_2_A3") (pintype "bidirectional"))
      (node (ref "TP_VREG") (pin "TP") (pinfunction "TP_TP") (pintype "input"))
    )
    (net (code "119") (name "unconnected-(ANT1-NC-Pad2)") (class "Default")
      (node (ref "ANT1") (pin "2") (pinfunction "NC_2") (pintype "no_connect"))
    )
    (net (code "120") (name "unconnected-(IC3-ASCL-Pad11)") (class "Default")
      (node (ref "IC3") (pin "11") (pinfunction "ASCL_11") (pintype "bidirectional"))
    )
    (net (code "121") (name "unconnected-(IC3-ASDA-Pad4)") (class "Default")
      (node (ref "IC3") (pin "4") (pinfunction "ASDA_4") (pintype "bidirectional"))
    )
    (net (code "122") (name "unconnected-(J1-Pad1)") (class "Default")
      (node (ref "J1") (pin "1") (pinfunction "1_1") (pintype "bidirectional"))
    )
    (net (code "123") (name "unconnected-(J1-Pad6)") (class "Default")
      (node (ref "J1") (pin "6") (pinfunction "6_6") (pintype "bidirectional"))
    )
    (net (code "124") (name "unconnected-(J1-Pad7)") (class "Default")
      (node (ref "J1") (pin "7") (pinfunction "7_7") (pintype "bidirectional"))
    )
    (net (code "125") (name "unconnected-(J4-SBU1-PadA8)") (class "Default")
      (node (ref "J4") (pin "A8") (pinfunction "SBU1_A8") (pintype "bidirectional"))
    )
    (net (code "126") (name "unconnected-(J4-SBU2-PadB8)") (class "Default")
      (node (ref "J4") (pin "B8") (pinfunction "SBU2_B8") (pintype "bidirectional"))
    )
    (net (code "127") (name "unconnected-(U1-DCCH-PadP$AB2)") (class "Default")
      (node (ref "U1") (pin "P$AB2") (pinfunction "DCCH_P$AB2") (pintype "bidirectional"))
    )
  )
)
